# SimplicityToSkeddAdapter.net
KiCad netlist of a schematic drawn in Altium Designer
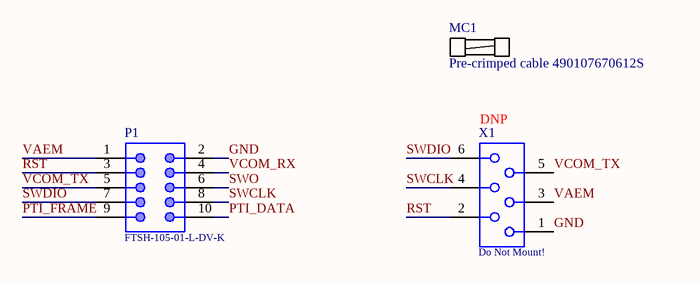
[diagram p0: SimplicityToSkeddAdapter.SchDoc]

(export (version "E")
  (design (tool "Eeschema 10.0.6"))
  (components
    (comp (ref "MC1")
      (value "Pre-crimped cable 490107670612S")
      (fields (field (name "PART NUMBER") "490107670612S"))
      (libsource (lib "Assembly_components") (part "Fuse"))
    )
    (comp (ref "P1")
      (value "FTSH-105-01-L-DV-K")
      (footprint "62101021021")
      (description "CONN HEADER SMD 10POS 1.27MM")
      (fields (field (name "MANUFACTURER") "Samtec"))
      (libsource (lib "Altium_WR-PHD_rev20a") (part "62101021021"))
    )
    (comp (ref "X1")
      (value "Do Not Mount!")
      (footprint "490107670612_Permanent Application")
      (description "WR-WST REDFIT IDC SKEDD, pitch 2.54mm, 6pins")
      (fields (field (name "PART NUMBER") "490107670612") (field (name "PUBLISHER") "Wurth Elektronik"))
      (libsource (lib "Altium_WR-WST (rev19b)") (part "490107670612"))
    )
  )
  (nets
    (net (code "1") (name "/GND") (class "Default")
      (node (ref "P1") (pin "2") (pinfunction "2_2") (pintype "passive"))
      (node (ref "X1") (pin "1") (pinfunction "1_1") (pintype "passive"))
    )
    (net (code "2") (name "/PTI_DATA") (class "Default")
      (node (ref "P1") (pin "10") (pinfunction "10_10") (pintype "passive"))
    )
    (net (code "3") (name "/PTI_FRAME") (class "Default")
      (node (ref "P1") (pin "9") (pinfunction "9_9") (pintype "passive"))
    )
    (net (code "4") (name "/RST") (class "Default")
      (node (ref "P1") (pin "3") (pinfunction "3_3") (pintype "passive"))
      (node (ref "X1") (pin "2") (pinfunction "2_2") (pintype "passive"))
    )
    (net (code "5") (name "/SWCLK") (class "Default")
      (node (ref "P1") (pin "8") (pinfunction "8_8") (pintype "passive"))
      (node (ref "X1") (pin "4") (pinfunction "4_4") (pintype "passive"))
    )
    (net (code "6") (name "/SWDIO") (class "Default")
      (node (ref "P1") (pin "7") (pinfunction "7_7") (pintype "passive"))
      (node (ref "X1") (pin "6") (pinfunction "6_6") (pintype "passive"))
    )
    (net (code "7") (name "/SWO") (class "Default")
      (node (ref "P1") (pin "6") (pinfunction "6_6") (pintype "passive"))
    )
    (net (code "8") (name "/VAEM") (class "Default")
      (node (ref "P1") (pin "1") (pinfunction "1_1") (pintype "passive"))
      (node (ref "X1") (pin "3") (pinfunction "3_3") (pintype "passive"))
    )
    (net (code "9") (name "/VCOM_RX") (class "Default")
      (node (ref "P1") (pin "4") (pinfunction "4_4") (pintype "passive"))
    )
    (net (code "10") (name "/VCOM_TX") (class "Default")
      (node (ref "P1") (pin "5") (pinfunction "5_5") (pintype "passive"))
      (node (ref "X1") (pin "5") (pinfunction "5_5") (pintype "passive"))
    )
  )
)
